# lvSdbSchematic.net
KiCad netlist of a schematic drawn in Altium Designer
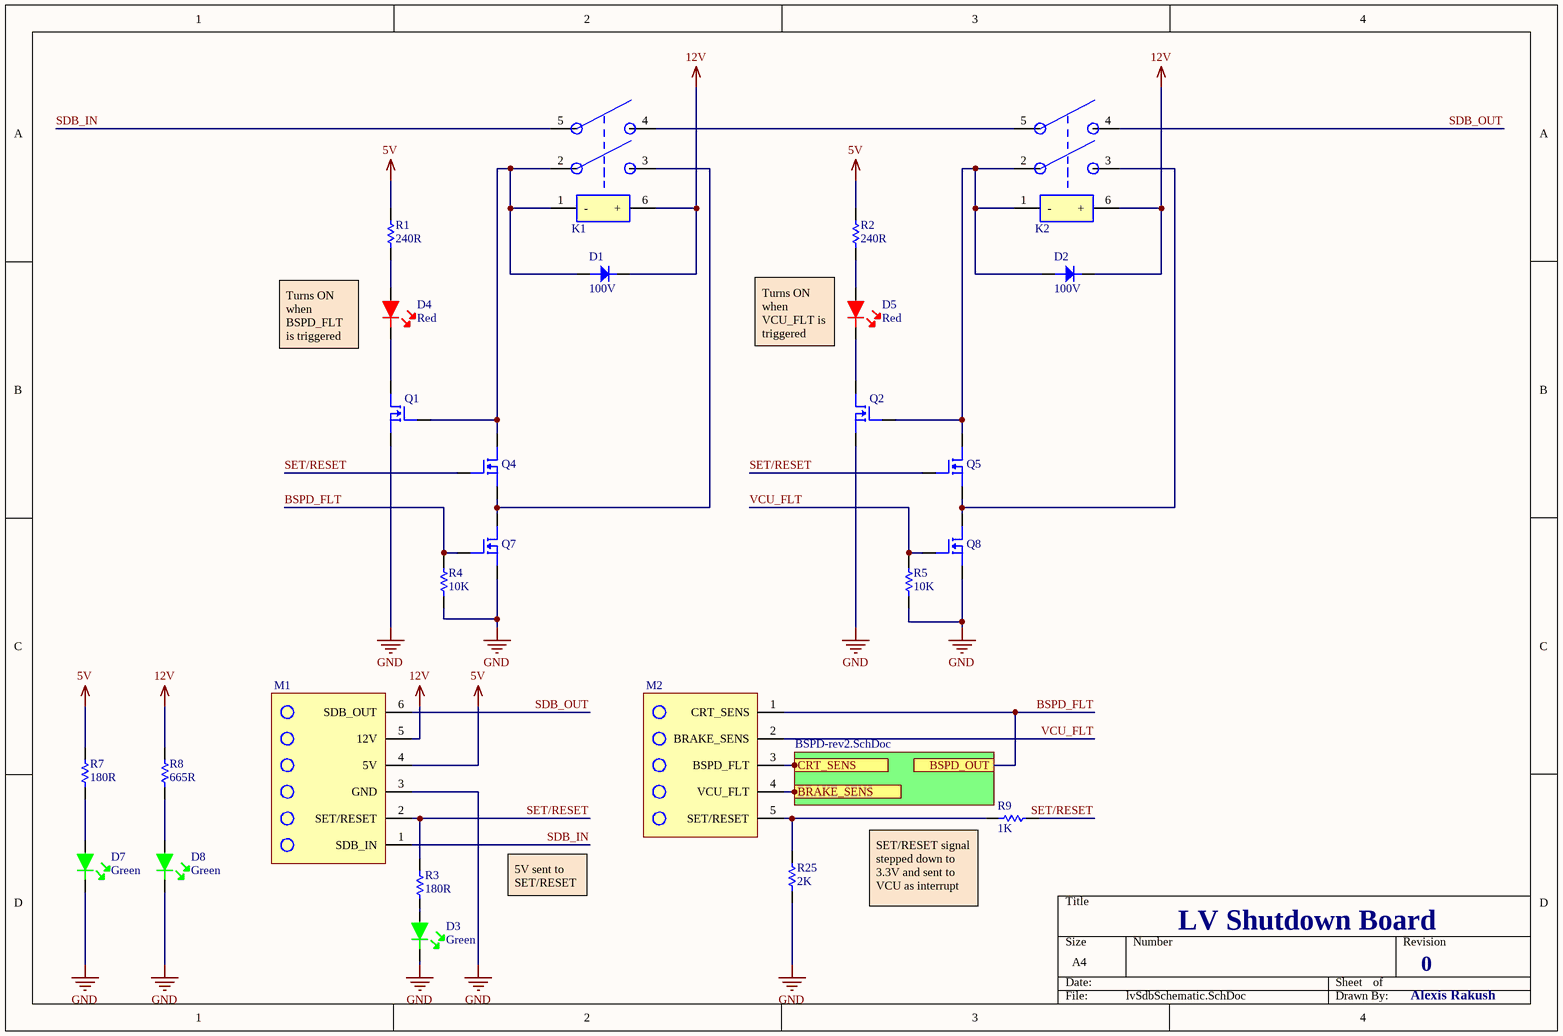
[diagram p0: lvSdbSchematic.SchDoc]

(export (version "E")
  (design (tool "Eeschema 10.0.6"))
  (components
    (comp (ref "D1")
      (value "100V")
      (footprint "DO-214AA")
      (description "DIODE GEN PURP 100V 3A DO214AA")
      (fields (field (name "MANUFACTURER") "MCC") (field (name "MANUFACTURER PART NUMBER") "S3BB-TP"))
      (libsource (lib "lvSdbSchLib") (part "Diode-100V-3A"))
    )
    (comp (ref "D2")
      (value "100V")
      (footprint "DO-214AA")
      (description "DIODE GEN PURP 100V 3A DO214AA")
      (fields (field (name "MANUFACTURER") "MCC") (field (name "MANUFACTURER PART NUMBER") "S3BB-TP"))
      (libsource (lib "lvSdbSchLib") (part "Diode-100V-3A"))
    )
    (comp (ref "D3")
      (value "Green")
      (footprint "LED-0603")
      (description "LED GREEN CLEAR 0603 SMD")
      (fields
        (field (name "MANUFACTURER") "Wurth Electronics")
        (field (name "MANUFACTURER PART NUMBER") "150060VS75000")
      )
      (libsource (lib "lvSdbSchLib") (part "LED-Green"))
    )
    (comp (ref "D4")
      (value "Red")
      (footprint "LED-0603")
      (description "LED RED CLEAR 0603 SMD")
      (fields
        (field (name "MANUFACTURER") "Wurth Electronics")
        (field (name "MANUFACTURER PART NUMBER") "150060RS75000")
      )
      (libsource (lib "lvSdbSchLib") (part "LED-Red"))
    )
    (comp (ref "D5")
      (value "Red")
      (footprint "LED-0603")
      (description "LED RED CLEAR 0603 SMD")
      (fields
        (field (name "MANUFACTURER") "Wurth Electronics")
        (field (name "MANUFACTURER PART NUMBER") "150060RS75000")
      )
      (libsource (lib "lvSdbSchLib") (part "LED-Red"))
    )
    (comp (ref "D7")
      (value "Green")
      (footprint "LED-0603")
      (description "LED GREEN CLEAR 0603 SMD")
      (fields
        (field (name "MANUFACTURER") "Wurth Electronics")
        (field (name "MANUFACTURER PART NUMBER") "150060VS75000")
      )
      (libsource (lib "lvSdbSchLib") (part "LED-Green"))
    )
    (comp (ref "D8")
      (value "Green")
      (footprint "LED-0603")
      (description "LED GREEN CLEAR 0603 SMD")
      (fields
        (field (name "MANUFACTURER") "Wurth Electronics")
        (field (name "MANUFACTURER PART NUMBER") "150060VS75000")
      )
      (libsource (lib "lvSdbSchLib") (part "LED-Green"))
    )
    (comp (ref "K1")
      (value "5-1419124-6")
      (footprint "RELAY DPST SDC")
      (description "General Purpose Relay, Osa Series, Power, Non Latching, Dpst-No, 12 Vdc, 3 A Rohs Compliant: Yes")
      (fields (field (name "MANUFACTURER") "TE Connectivity"))
      (libsource (lib "lvSdbSchLib") (part "5-1419124-6"))
    )
    (comp (ref "K2")
      (value "5-1419124-6")
      (footprint "RELAY DPST SDC")
      (description "General Purpose Relay, Osa Series, Power, Non Latching, Dpst-No, 12 Vdc, 3 A Rohs Compliant: Yes")
      (fields (field (name "MANUFACTURER") "TE Connectivity"))
      (libsource (lib "lvSdbSchLib") (part "5-1419124-6"))
    )
    (comp (ref "M1")
      (value "WM10676-ND")
      (footprint "6-PIN MOLEX")
      (description "CONN HEADER VERT 6POS 3MM")
      (libsource (lib "lvSdbSchLib") (part "6 PIN HDR"))
    )
    (comp (ref "M2")
      (value "WM10672-ND")
      (footprint "5-PIN MOLEX")
      (description "CONN HEADER VERT 5POS 3MM")
      (libsource (lib "lvSdbSchLib") (part "5 PIN HDR"))
    )
    (comp (ref "Q1")
      (value "DMN6140L-13DICT-ND")
      (footprint "SOT-23-3")
      (description "MOSFET N-CH 60V 1.6A SOT23")
      (fields (field (name "MANUFACTURER") "Diodes") (field (name "MANUFACTURER PART NUMBER") "DMN6140L-13"))
      (libsource (lib "lvSdbSchLib") (part "N-FET-60V-1.6A"))
    )
    (comp (ref "Q2")
      (value "DMN6140L-13DICT-ND")
      (footprint "SOT-23-3")
      (description "MOSFET N-CH 60V 1.6A SOT23")
      (fields (field (name "MANUFACTURER") "Diodes") (field (name "MANUFACTURER PART NUMBER") "DMN6140L-13"))
      (libsource (lib "lvSdbSchLib") (part "N-FET-60V-1.6A"))
    )
    (comp (ref "Q4")
      (value "DMN6140L-13DICT-ND")
      (footprint "SOT-23-3")
      (description "MOSFET N-CH 60V 1.6A SOT23")
      (fields (field (name "MANUFACTURER") "Diodes") (field (name "MANUFACTURER PART NUMBER") "DMN6140L-13"))
      (libsource (lib "lvSdbSchLib") (part "N-FET-60V-1.6A"))
    )
    (comp (ref "Q5")
      (value "DMN6140L-13DICT-ND")
      (footprint "SOT-23-3")
      (description "MOSFET N-CH 60V 1.6A SOT23")
      (fields (field (name "MANUFACTURER") "Diodes") (field (name "MANUFACTURER PART NUMBER") "DMN6140L-13"))
      (libsource (lib "lvSdbSchLib") (part "N-FET-60V-1.6A"))
    )
    (comp (ref "Q7")
      (value "DMN6140L-13DICT-ND")
      (footprint "SOT-23-3")
      (description "MOSFET N-CH 60V 1.6A SOT23")
      (fields (field (name "MANUFACTURER") "Diodes") (field (name "MANUFACTURER PART NUMBER") "DMN6140L-13"))
      (libsource (lib "lvSdbSchLib") (part "N-FET-60V-1.6A"))
    )
    (comp (ref "Q8")
      (value "DMN6140L-13DICT-ND")
      (footprint "SOT-23-3")
      (description "MOSFET N-CH 60V 1.6A SOT23")
      (fields (field (name "MANUFACTURER") "Diodes") (field (name "MANUFACTURER PART NUMBER") "DMN6140L-13"))
      (libsource (lib "lvSdbSchLib") (part "N-FET-60V-1.6A"))
    )
    (comp (ref "R1")
      (value "240R")
      (footprint "RES-0603")
      (description "RES 240 OHM 1% 1/10W 0603")
      (fields
        (field (name "MANUFACTURER") "Stackpole Electronics")
        (field (name "MANUFACTURER PART NUMBER") "RMCF0603FT240R")
      )
      (libsource (lib "lvSdbSchLib") (part "0603-240R"))
    )
    (comp (ref "R2")
      (value "240R")
      (footprint "RES-0603")
      (description "RES 240 OHM 1% 1/10W 0603")
      (fields
        (field (name "MANUFACTURER") "Stackpole Electronics")
        (field (name "MANUFACTURER PART NUMBER") "RMCF0603FT240R")
      )
      (libsource (lib "lvSdbSchLib") (part "0603-240R"))
    )
    (comp (ref "R3")
      (value "180R")
      (footprint "RES-0603")
      (description "RES SMD 180 OHM 1% 1/10W 0603")
      (fields
        (field (name "MANUFACTURER") "TE Connectivity")
        (field (name "MANUFACTURER PART NUMBER") "CRGCQ0603F180R")
      )
      (libsource (lib "lvSdbSchLib") (part "0603-180R"))
    )
    (comp (ref "R4")
      (value "10K")
      (footprint "RES-0603")
      (description "RES SMD 10K OHM 5% 1/10W 0603")
      (fields
        (field (name "MANUFACTURER") "Yageo")
        (field (name "MANUFACTURER PART NUMBER") "RC0603JR-0710KL")
      )
      (libsource (lib "lvSdbSchLib") (part "0603-10KR"))
    )
    (comp (ref "R5")
      (value "10K")
      (footprint "RES-0603")
      (description "RES SMD 10K OHM 5% 1/10W 0603")
      (fields
        (field (name "MANUFACTURER") "Yageo")
        (field (name "MANUFACTURER PART NUMBER") "RC0603JR-0710KL")
      )
      (libsource (lib "lvSdbSchLib") (part "0603-10KR"))
    )
    (comp (ref "R7")
      (value "180R")
      (footprint "RES-0603")
      (description "RES SMD 180 OHM 1% 1/10W 0603")
      (fields
        (field (name "MANUFACTURER") "TE Connectivity")
        (field (name "MANUFACTURER PART NUMBER") "CRGCQ0603F180R")
      )
      (libsource (lib "lvSdbSchLib") (part "0603-180R"))
    )
    (comp (ref "R8")
      (value "665R")
      (footprint "RES-0603")
      (description "RES SMD 665 OHM 1% 1/10W 0603")
      (fields
        (field (name "MANUFACTURER") "Yageo")
        (field (name "MANUFACTURER PART NUMBER") "RC0603FR-07665RL")
      )
      (libsource (lib "lvSdbSchLib") (part "0603-665R"))
    )
    (comp (ref "R9")
      (value "1K")
      (footprint "RES-0603")
      (description "RES SMD 1K OHM 1% 1/10W 0603")
      (fields
        (field (name "MANUFACTURER") "Vishay Dale")
        (field (name "MANUFACTURER PART NUMBER") "CRCW06031K00FKEA")
      )
      (libsource (lib "lvSdbSchLib") (part "0603-1KR"))
    )
    (comp (ref "R25")
      (value "2K")
      (footprint "RES-0603")
      (description "RES SMD 2K OHM 1% 1/4W 0603")
      (fields
        (field (name "MANUFACTURER") "Vishay Dale")
        (field (name "MANUFACTURER PART NUMBER") "CRCW06032K00FKEAHP")
      )
      (libsource (lib "lvSdbSchLib") (part "0603-2KR"))
    )
  )
  (nets
    (net (code "1") (name "/BRAKE_SENS") (class "Default")
      (node (ref "M2") (pin "4") (pinfunction "VCU_FLT_4") (pintype "passive"))
    )
    (net (code "2") (name "/BSPD_FLT") (class "Default")
      (node (ref "M2") (pin "1") (pinfunction "CRT_SENS_1") (pintype "passive"))
      (node (ref "Q7") (pin "1") (pinfunction "1_1") (pintype "passive"))
      (node (ref "R4") (pin "2") (pinfunction "2_2") (pintype "passive"))
    )
    (net (code "3") (name "/CRT_SENS") (class "Default")
      (node (ref "M2") (pin "3") (pinfunction "BSPD_FLT_3") (pintype "passive"))
    )
    (net (code "4") (name "/SDB_IN") (class "Default")
      (node (ref "K1") (pin "5") (pintype "passive"))
      (node (ref "M1") (pin "1") (pinfunction "SDB_IN_1") (pintype "passive"))
    )
    (net (code "5") (name "/SDB_OUT") (class "Default")
      (node (ref "K2") (pin "4") (pintype "passive"))
      (node (ref "M1") (pin "6") (pinfunction "SDB_OUT_6") (pintype "passive"))
    )
    (net (code "6") (name "/SET{slash}RESET") (class "Default")
      (node (ref "M1") (pin "2") (pinfunction "SET/RESET_2") (pintype "passive"))
      (node (ref "Q4") (pin "1") (pinfunction "1_1") (pintype "passive"))
      (node (ref "Q5") (pin "1") (pinfunction "1_1") (pintype "passive"))
      (node (ref "R3") (pin "1") (pinfunction "1_1") (pintype "passive"))
      (node (ref "R9") (pin "2") (pinfunction "2_2") (pintype "passive"))
    )
    (net (code "7") (name "/VCU_FLT") (class "Default")
      (node (ref "M2") (pin "2") (pinfunction "BRAKE_SENS_2") (pintype "passive"))
      (node (ref "Q8") (pin "1") (pinfunction "1_1") (pintype "passive"))
      (node (ref "R5") (pin "2") (pinfunction "2_2") (pintype "passive"))
    )
    (net (code "8") (name "5V") (class "Default")
      (node (ref "M1") (pin "4") (pinfunction "5V_4") (pintype "passive"))
      (node (ref "R1") (pin "2") (pinfunction "2_2") (pintype "passive"))
      (node (ref "R2") (pin "2") (pinfunction "2_2") (pintype "passive"))
      (node (ref "R7") (pin "2") (pinfunction "2_2") (pintype "passive"))
    )
    (net (code "9") (name "12V") (class "Default")
      (node (ref "D1") (pin "1") (pinfunction "1_1") (pintype "passive"))
      (node (ref "D2") (pin "1") (pinfunction "1_1") (pintype "passive"))
      (node (ref "K1") (pin "6") (pinfunction "+_6") (pintype "passive"))
      (node (ref "K2") (pin "6") (pinfunction "+_6") (pintype "passive"))
      (node (ref "M1") (pin "5") (pinfunction "12V_5") (pintype "passive"))
      (node (ref "R8") (pin "2") (pinfunction "2_2") (pintype "passive"))
    )
    (net (code "10") (name "GND") (class "Default")
      (node (ref "D3") (pin "2") (pinfunction "2_2") (pintype "passive"))
      (node (ref "D7") (pin "2") (pinfunction "2_2") (pintype "passive"))
      (node (ref "D8") (pin "2") (pinfunction "2_2") (pintype "passive"))
      (node (ref "M1") (pin "3") (pinfunction "GND_3") (pintype "passive"))
      (node (ref "Q1") (pin "3") (pinfunction "3_3") (pintype "passive"))
      (node (ref "Q2") (pin "3") (pinfunction "3_3") (pintype "passive"))
      (node (ref "Q7") (pin "3") (pinfunction "3_3") (pintype "passive"))
      (node (ref "Q8") (pin "3") (pinfunction "3_3") (pintype "passive"))
      (node (ref "R25") (pin "1") (pinfunction "1_1") (pintype "passive"))
      (node (ref "R4") (pin "1") (pinfunction "1_1") (pintype "passive"))
      (node (ref "R5") (pin "1") (pinfunction "1_1") (pintype "passive"))
    )
    (net (code "11") (name "Net-(D3-Pad1)") (class "Default")
      (node (ref "D3") (pin "1") (pinfunction "1_1") (pintype "passive"))
      (node (ref "R3") (pin "2") (pinfunction "2_2") (pintype "passive"))
    )
    (net (code "12") (name "Net-(D4-Pad1)") (class "Default")
      (node (ref "D4") (pin "1") (pinfunction "1_1") (pintype "passive"))
      (node (ref "R1") (pin "1") (pinfunction "1_1") (pintype "passive"))
    )
    (net (code "13") (name "Net-(D4-Pad2)") (class "Default")
      (node (ref "D4") (pin "2") (pinfunction "2_2") (pintype "passive"))
      (node (ref "Q1") (pin "2") (pinfunction "2_2") (pintype "passive"))
    )
    (net (code "14") (name "Net-(D5-Pad1)") (class "Default")
      (node (ref "D5") (pin "1") (pinfunction "1_1") (pintype "passive"))
      (node (ref "R2") (pin "1") (pinfunction "1_1") (pintype "passive"))
    )
    (net (code "15") (name "Net-(D5-Pad2)") (class "Default")
      (node (ref "D5") (pin "2") (pinfunction "2_2") (pintype "passive"))
      (node (ref "Q2") (pin "2") (pinfunction "2_2") (pintype "passive"))
    )
    (net (code "16") (name "Net-(D7-Pad1)") (class "Default")
      (node (ref "D7") (pin "1") (pinfunction "1_1") (pintype "passive"))
      (node (ref "R7") (pin "1") (pinfunction "1_1") (pintype "passive"))
    )
    (net (code "17") (name "Net-(D8-Pad1)") (class "Default")
      (node (ref "D8") (pin "1") (pinfunction "1_1") (pintype "passive"))
      (node (ref "R8") (pin "1") (pinfunction "1_1") (pintype "passive"))
    )
    (net (code "18") (name "Net-(K1--)") (class "Default")
      (node (ref "D1") (pin "2") (pinfunction "2_2") (pintype "passive"))
      (node (ref "K1") (pin "1") (pinfunction "-_1") (pintype "passive"))
      (node (ref "K1") (pin "2") (pintype "passive"))
      (node (ref "Q1") (pin "1") (pinfunction "1_1") (pintype "passive"))
      (node (ref "Q4") (pin "2") (pinfunction "2_2") (pintype "passive"))
    )
    (net (code "19") (name "Net-(K1-Pad3)") (class "Default")
      (node (ref "K1") (pin "3") (pintype "passive"))
      (node (ref "Q4") (pin "3") (pinfunction "3_3") (pintype "passive"))
      (node (ref "Q7") (pin "2") (pinfunction "2_2") (pintype "passive"))
    )
    (net (code "20") (name "Net-(K1-Pad4)") (class "Default")
      (node (ref "K1") (pin "4") (pintype "passive"))
      (node (ref "K2") (pin "5") (pintype "passive"))
    )
    (net (code "21") (name "Net-(K2--)") (class "Default")
      (node (ref "D2") (pin "2") (pinfunction "2_2") (pintype "passive"))
      (node (ref "K2") (pin "1") (pinfunction "-_1") (pintype "passive"))
      (node (ref "K2") (pin "2") (pintype "passive"))
      (node (ref "Q2") (pin "1") (pinfunction "1_1") (pintype "passive"))
      (node (ref "Q5") (pin "2") (pinfunction "2_2") (pintype "passive"))
    )
    (net (code "22") (name "Net-(K2-Pad3)") (class "Default")
      (node (ref "K2") (pin "3") (pintype "passive"))
      (node (ref "Q5") (pin "3") (pinfunction "3_3") (pintype "passive"))
      (node (ref "Q8") (pin "2") (pinfunction "2_2") (pintype "passive"))
    )
    (net (code "23") (name "Net-(M2-SET{slash}RESET)") (class "Default")
      (node (ref "M2") (pin "5") (pinfunction "SET/RESET_5") (pintype "passive"))
      (node (ref "R25") (pin "2") (pinfunction "2_2") (pintype "passive"))
      (node (ref "R9") (pin "1") (pinfunction "1_1") (pintype "passive"))
    )
  )
)
